# PWMswitch.net
KiCad netlist of a schematic drawn in Altium Designer
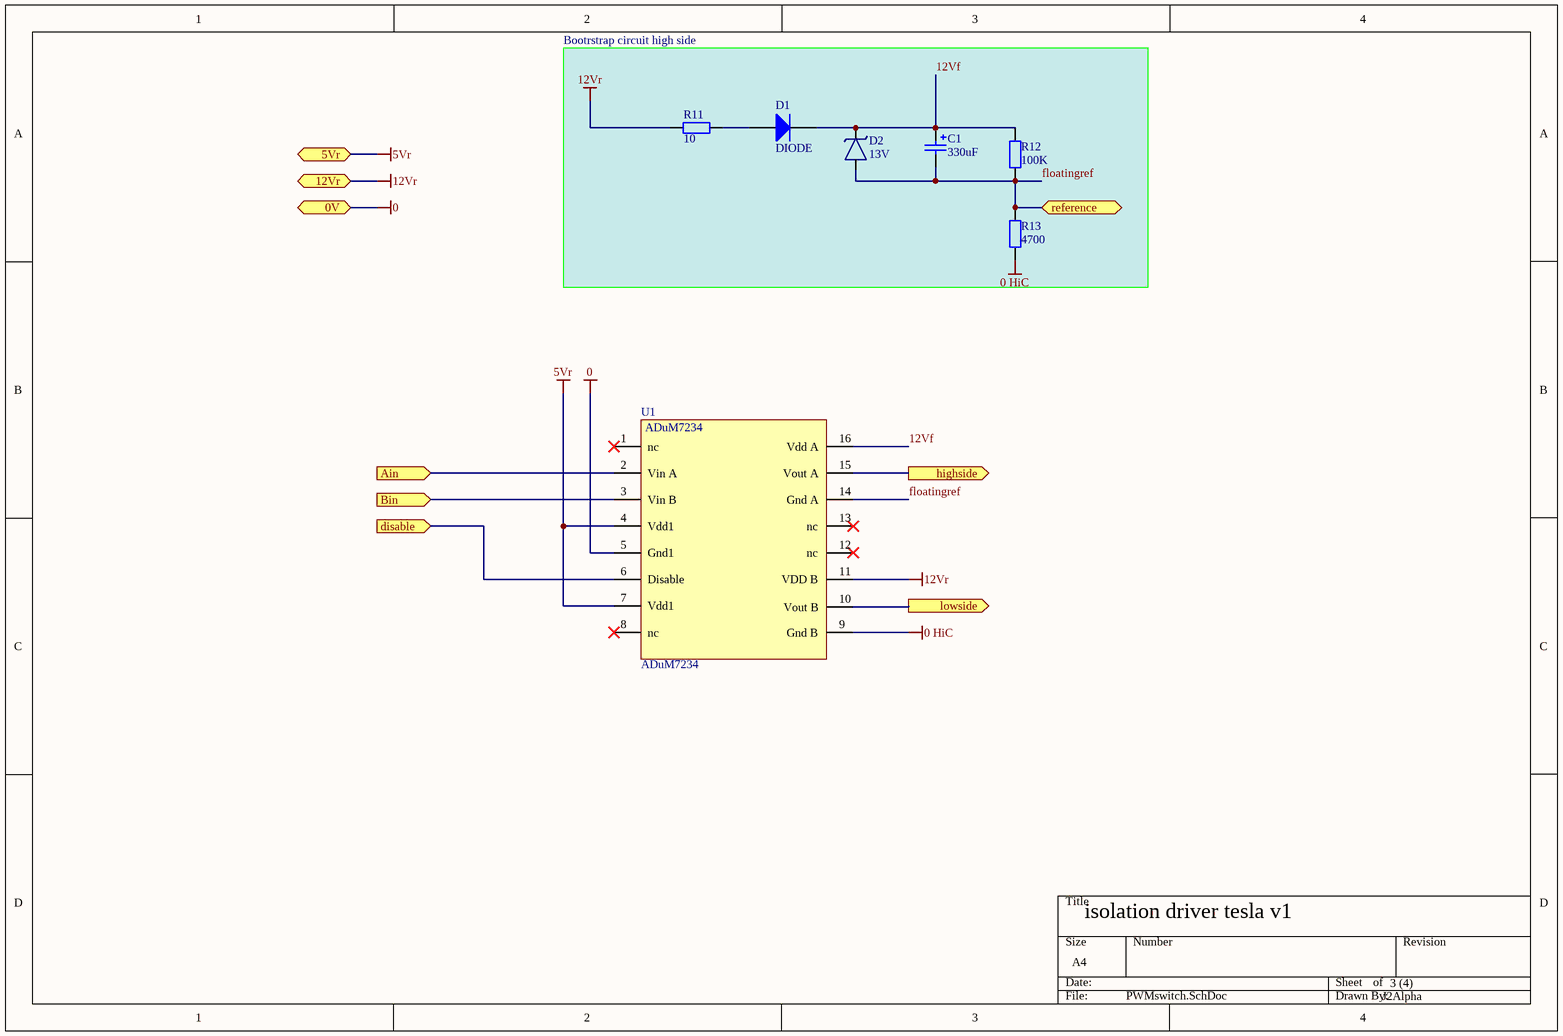
[diagram p0: PWMswitch.SchDoc]

(export (version "E")
  (design (tool "Eeschema 10.0.6"))
  (components
    (comp (ref "C1")
      (value "330uF")
      (footprint "1608[0603]")
      (description "Capacitor polorized")
      (fields (field (name "PUBLISHER") "Altium Limited"))
      (libsource (lib "DARE") (part "Cap_pol_mm"))
    )
    (comp (ref "D1")
      (value "DIODE")
      (footprint "SMB")
      (description "regular diode")
      (libsource (lib "DARE") (part "DIODE"))
    )
    (comp (ref "D2")
      (value "13V")
      (footprint "SOT95P240-3N")
      (description "Zener")
      (libsource (lib "teslaeggspecificparts") (part "zennerdiode sot23"))
    )
    (comp (ref "R11")
      (value "10")
      (footprint "1005[0402]")
      (description "Resistor")
      (fields (field (name "PUBLISHER") "Altium Limited"))
      (libsource (lib "DARE") (part "Res_mm"))
    )
    (comp (ref "R12")
      (value "100K")
      (footprint "1005[0402]")
      (description "Resistor")
      (fields (field (name "PUBLISHER") "Altium Limited"))
      (libsource (lib "") (part "Res_mm_1"))
    )
    (comp (ref "R13")
      (value "4700")
      (footprint "1005[0402]")
      (description "Resistor")
      (fields (field (name "PUBLISHER") "Altium Limited"))
      (libsource (lib "") (part "Res_mm_1"))
    )
    (comp (ref "U1")
      (value "ADuM7234")
      (footprint "SOIC127P600-16N")
      (description "ADuM7234 dual isolated gate driver")
      (libsource (lib "teslaeggspecificparts") (part "ADuM7234"))
    )
  )
  (nets
    (net (code "1") (name "/12Vf") (class "Default")
      (node (ref "C1") (pin "1") (pinfunction "1_1") (pintype "passive"))
      (node (ref "D1") (pin "K") (pinfunction "K_K") (pintype "passive"))
      (node (ref "D2") (pin "3") (pinfunction "3_3") (pintype "passive"))
      (node (ref "R12") (pin "2") (pinfunction "2_2") (pintype "passive"))
      (node (ref "U1") (pin "16") (pinfunction "Vdd_A_16") (pintype "passive"))
    )
    (net (code "2") (name "/Ain") (class "Default")
      (node (ref "U1") (pin "2") (pinfunction "Vin_A_2") (pintype "passive"))
    )
    (net (code "3") (name "/Bin") (class "Default")
      (node (ref "U1") (pin "3") (pinfunction "Vin_B_3") (pintype "passive"))
    )
    (net (code "4") (name "/disable") (class "Default")
      (node (ref "U1") (pin "6") (pinfunction "Disable_6") (pintype "passive"))
    )
    (net (code "5") (name "/floatingref") (class "Default")
      (node (ref "C1") (pin "2") (pinfunction "2_2") (pintype "passive"))
      (node (ref "D2") (pin "1") (pinfunction "19_1") (pintype "passive"))
      (node (ref "R12") (pin "1") (pinfunction "1_1") (pintype "passive"))
      (node (ref "R13") (pin "2") (pinfunction "2_2") (pintype "passive"))
      (node (ref "U1") (pin "14") (pinfunction "Gnd_A_14") (pintype "passive"))
    )
    (net (code "6") (name "/highside") (class "Default")
      (node (ref "U1") (pin "15") (pinfunction "Vout_A_15") (pintype "passive"))
    )
    (net (code "7") (name "/lowside") (class "Default")
      (node (ref "U1") (pin "10") (pinfunction "Vout_B_10") (pintype "passive"))
    )
    (net (code "8") (name "0") (class "Default")
      (node (ref "U1") (pin "5") (pinfunction "Gnd1_5") (pintype "passive"))
    )
    (net (code "9") (name "0 HiC") (class "Default")
      (node (ref "R13") (pin "1") (pinfunction "1_1") (pintype "passive"))
      (node (ref "U1") (pin "9") (pinfunction "Gnd_B_9") (pintype "passive"))
    )
    (net (code "10") (name "5Vr") (class "Default")
      (node (ref "U1") (pin "4") (pinfunction "Vdd1_4") (pintype "passive"))
      (node (ref "U1") (pin "7") (pinfunction "Vdd1_7") (pintype "passive"))
    )
    (net (code "11") (name "12Vr") (class "Default")
      (node (ref "R11") (pin "1") (pinfunction "1_1") (pintype "passive"))
      (node (ref "U1") (pin "11") (pinfunction "VDD_B_11") (pintype "passive"))
    )
    (net (code "12") (name "Net-(D1-PadA)") (class "Default")
      (node (ref "D1") (pin "A") (pinfunction "A_A") (pintype "passive"))
      (node (ref "R11") (pin "2") (pinfunction "2_2") (pintype "passive"))
    )
    (net (code "13") (name "unconnected-(D2-Pad2)") (class "Default")
      (node (ref "D2") (pin "2") (pinfunction "2_2") (pintype "passive"))
    )
    (net (code "14") (name "unconnected-(U1-nc-Pad1)") (class "Default")
      (node (ref "U1") (pin "1") (pinfunction "nc_1") (pintype "passive+no_connect"))
    )
    (net (code "15") (name "unconnected-(U1-nc-Pad8)") (class "Default")
      (node (ref "U1") (pin "8") (pinfunction "nc_8") (pintype "passive+no_connect"))
    )
    (net (code "16") (name "unconnected-(U1-nc-Pad12)") (class "Default")
      (node (ref "U1") (pin "12") (pinfunction "nc_12") (pintype "passive+no_connect"))
    )
    (net (code "17") (name "unconnected-(U1-nc-Pad13)") (class "Default")
      (node (ref "U1") (pin "13") (pinfunction "nc_13") (pintype "passive+no_connect"))
    )
  )
)
